# CLKB_power_regulators.net
KiCad netlist of a schematic drawn in Altium Designer
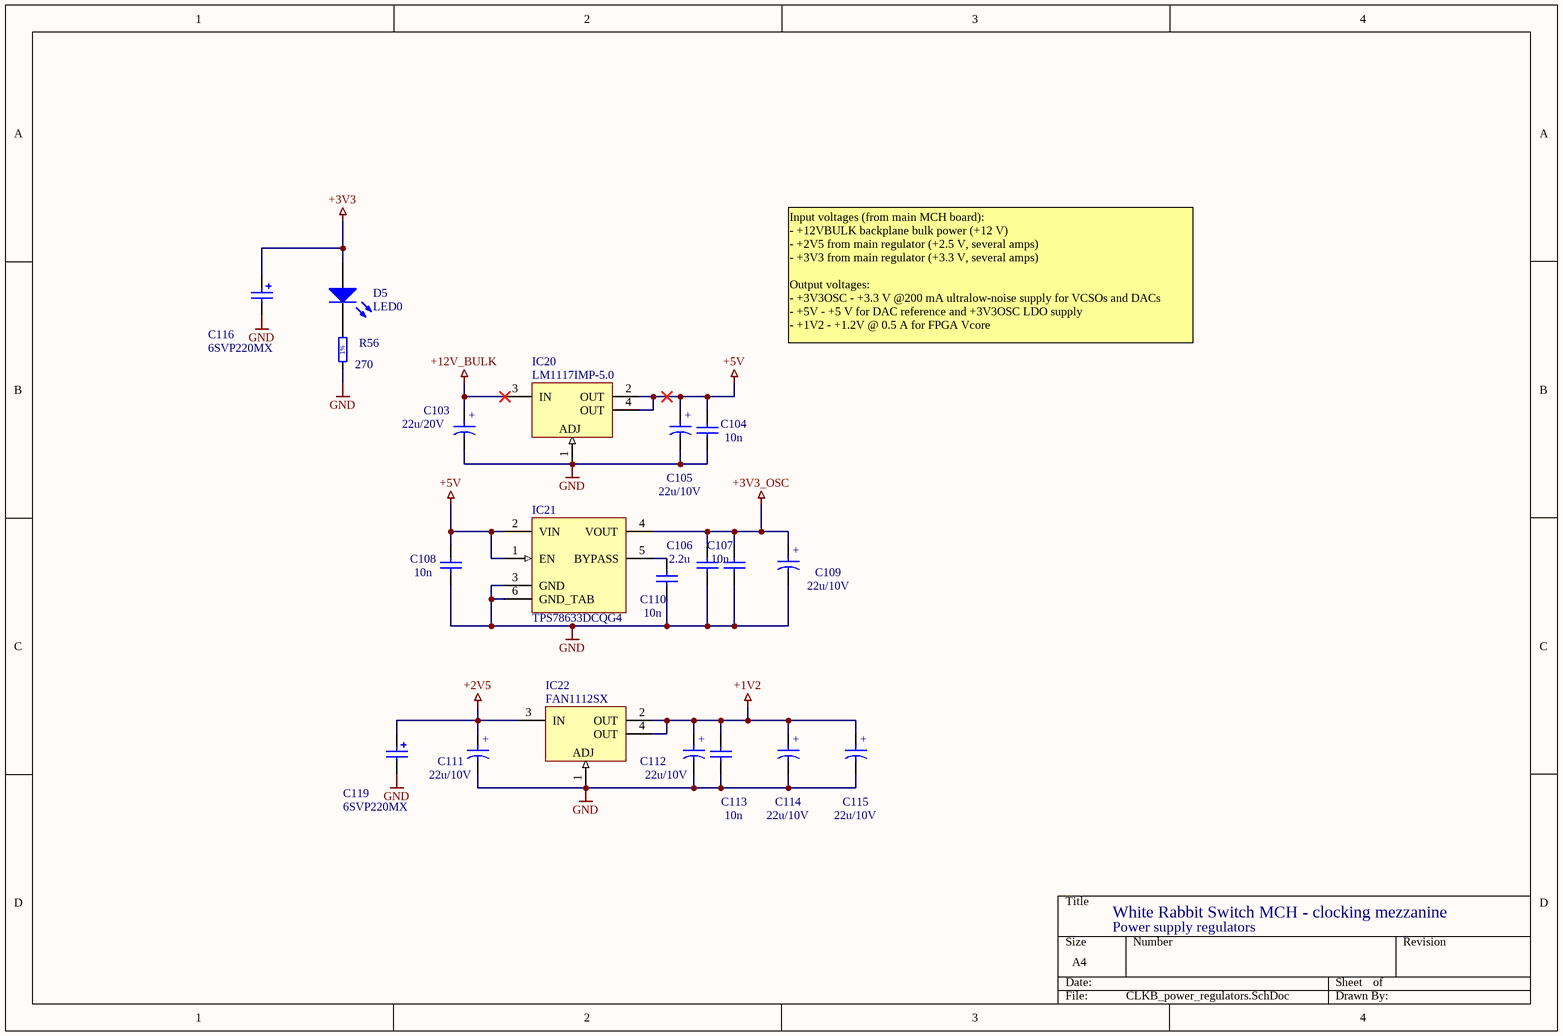
[diagram p0: CLKB_power_regulators.SchDoc]

(export (version "E")
  (design (tool "Eeschema 10.0.6"))
  (components
    (comp (ref "C103")
      (value "22u/20V")
      (footprint "CAPMP3528X210N")
      (description "Polarised capacitor")
      (fields
        (field (name "PART NUMBER") "CTE3528-21_22UF_20V_10%")
        (field (name "VOLTAGE") "20V")
        (field (name "AUTHOR") "CERN DEM JLC")
      )
      (libsource (lib "Capacitors") (part "Capacitor - polarized"))
    )
    (comp (ref "C104")
      (value "22u/10V")
      (footprint "CAPMP3216X180N")
      (description "Polarised capacitor")
      (fields
        (field (name "PART NUMBER") "CTE3216-18_22UF_10V_10%")
        (field (name "VOLTAGE") "10V")
        (field (name "AUTHOR") "CERN DEM JLC")
      )
      (libsource (lib "Capacitors") (part "Capacitor - polarized"))
    )
    (comp (ref "C105")
      (value "10n")
      (footprint "CAPC1608X87N")
      (description "Non-polarised capacitor")
      (fields
        (field (name "PART NUMBER") "CC0603_10NF_50V_10%_X7R")
        (field (name "VOLTAGE") "50V")
        (field (name "AUTHOR") "CERN DEM JLC")
      )
      (libsource (lib "Capacitors") (part "Capacitor - non polarized"))
    )
    (comp (ref "C106")
      (value "2.2u")
      (footprint "CAPC2012X135N")
      (description "Non-polarised capacitor")
      (fields
        (field (name "PART NUMBER") "CC0805_2.2UF_16V_10%_X7R")
        (field (name "VOLTAGE") "16V")
        (field (name "AUTHOR") "CERN DEM JLC")
      )
      (libsource (lib "Capacitors") (part "Capacitor - non polarized"))
    )
    (comp (ref "C107")
      (value "10n")
      (footprint "CAPC1608X87N")
      (description "Non-polarised capacitor")
      (fields
        (field (name "PART NUMBER") "CC0603_10NF_50V_10%_X7R")
        (field (name "VOLTAGE") "50V")
        (field (name "AUTHOR") "CERN DEM JLC")
      )
      (libsource (lib "Capacitors") (part "Capacitor - non polarized"))
    )
    (comp (ref "C108")
      (value "10n")
      (footprint "CAPC1608X87N")
      (description "Non-polarised capacitor")
      (fields
        (field (name "PART NUMBER") "CC0603_10NF_50V_10%_X7R")
        (field (name "VOLTAGE") "50V")
        (field (name "AUTHOR") "CERN DEM JLC")
      )
      (libsource (lib "Capacitors") (part "Capacitor - non polarized"))
    )
    (comp (ref "C109")
      (value "22u/10V")
      (footprint "CAPMP3216X180N")
      (description "Polarised capacitor")
      (fields
        (field (name "PART NUMBER") "CTE3216-18_22UF_10V_10%")
        (field (name "VOLTAGE") "10V")
        (field (name "AUTHOR") "CERN DEM JLC")
      )
      (libsource (lib "Capacitors") (part "Capacitor - polarized"))
    )
    (comp (ref "C110")
      (value "10n")
      (footprint "CAPC1608X87N")
      (description "Non-polarised capacitor")
      (fields
        (field (name "PART NUMBER") "CC0603_10NF_50V_10%_X7R")
        (field (name "VOLTAGE") "50V")
        (field (name "AUTHOR") "CERN DEM JLC")
      )
      (libsource (lib "Capacitors") (part "Capacitor - non polarized"))
    )
    (comp (ref "C111")
      (value "22u/10V")
      (footprint "CAPMP3216X180N")
      (description "Polarised capacitor")
      (fields
        (field (name "PART NUMBER") "CTE3216-18_22UF_10V_10%")
        (field (name "VOLTAGE") "10V")
        (field (name "AUTHOR") "CERN DEM JLC")
      )
      (libsource (lib "Capacitors") (part "Capacitor - polarized"))
    )
    (comp (ref "C112")
      (value "10n")
      (footprint "CAPC1608X87N")
      (description "Non-polarised capacitor")
      (fields
        (field (name "PART NUMBER") "CC0603_10NF_50V_10%_X7R")
        (field (name "VOLTAGE") "50V")
        (field (name "AUTHOR") "CERN DEM JLC")
      )
      (libsource (lib "Capacitors") (part "Capacitor - non polarized"))
    )
    (comp (ref "C113")
      (value "22u/10V")
      (footprint "CAPMP3216X180N")
      (description "Polarised capacitor")
      (fields
        (field (name "PART NUMBER") "CTE3216-18_22UF_10V_10%")
        (field (name "VOLTAGE") "10V")
        (field (name "AUTHOR") "CERN DEM JLC")
      )
      (libsource (lib "Capacitors") (part "Capacitor - polarized"))
    )
    (comp (ref "C114")
      (value "22u/10V")
      (footprint "CAPMP3216X180N")
      (description "Polarised capacitor")
      (fields
        (field (name "PART NUMBER") "CTE3216-18_22UF_10V_10%")
        (field (name "VOLTAGE") "10V")
        (field (name "AUTHOR") "CERN DEM JLC")
      )
      (libsource (lib "Capacitors") (part "Capacitor - polarized"))
    )
    (comp (ref "C115")
      (value "22u/10V")
      (footprint "CAPMP3216X180N")
      (description "Polarised capacitor")
      (fields
        (field (name "PART NUMBER") "CTE3216-18_22UF_10V_10%")
        (field (name "VOLTAGE") "10V")
        (field (name "AUTHOR") "CERN DEM JLC")
      )
      (libsource (lib "Capacitors") (part "Capacitor - polarized"))
    )
    (comp (ref "C116")
      (value "6SVP220MX")
      (footprint "OSCON_E7")
      (description "Polarized Capacitor (Radial)")
      (fields (field (name "Comment") "Cap Pol1") (field (name "PUBLISHER") "Altium Limited"))
      (libsource (lib "wr_switch") (part "Cap Pol1"))
    )
    (comp (ref "C119")
      (value "6SVP220MX")
      (footprint "OSCON_E7")
      (description "Polarized Capacitor (Radial)")
      (fields (field (name "Comment") "Cap Pol1") (field (name "PUBLISHER") "Altium Limited"))
      (libsource (lib "wr_switch") (part "Cap Pol1"))
    )
    (comp (ref "D5")
      (value "LED0")
      (footprint "CD1608-0603")
      (description "Red chip LED")
      (fields (field (name "PUBLISHER") "Altium Limited"))
      (libsource (lib "Miscellaneous Devices") (part "LED0"))
    )
    (comp (ref "IC20")
      (value "LM1117IMP-5.0")
      (footprint "SOT223-4L")
      (description "Three-Terminal Adjustable Output Positive Voltage Regulator")
      (fields (field (name "Comment") "LM1117") (field (name "PUBLISHER") "Altium Limited"))
      (libsource (lib "wr_switch") (part "1117"))
    )
    (comp (ref "IC21")
      (value "TPS78633DCQG4")
      (footprint "SOT223-6L")
      (description "TI low noise LDO, 1A load")
      (fields (field (name "Comment") "TPS786xx"))
      (libsource (lib "wr_switch") (part "TPS786xx"))
    )
    (comp (ref "IC22")
      (value "FAN1112SX")
      (footprint "SOT223-4L")
      (description "Three-Terminal Adjustable Output Positive Voltage Regulator")
      (fields (field (name "Comment") "LM1117") (field (name "PUBLISHER") "Altium Limited"))
      (libsource (lib "wr_switch") (part "1117"))
    )
    (comp (ref "R56")
      (value "270")
      (footprint "RESC1608X55N")
      (description "Resistor - 1%")
      (fields
        (field (name "PART NUMBER") "R0603_270R_1%_0.1W_100PPM")
        (field (name "POWER") "0.1W")
        (field (name "AUTHOR") "CERN DEM JLC")
      )
      (libsource (lib "Resistors") (part "Resistor - 1%"))
    )
  )
  (nets
    (net (code "1") (name "+1V2") (class "Default")
      (node (ref "C112") (pin "2") (pinfunction "2_2") (pintype "passive"))
      (node (ref "C113") (pin "1") (pinfunction "1_1") (pintype "passive"))
      (node (ref "C114") (pin "1") (pinfunction "1_1") (pintype "passive"))
      (node (ref "C115") (pin "1") (pinfunction "1_1") (pintype "passive"))
      (node (ref "IC22") (pin "2") (pinfunction "OUT_2") (pintype "power_in"))
      (node (ref "IC22") (pin "4") (pinfunction "OUT_4") (pintype "power_in"))
    )
    (net (code "2") (name "+2V5") (class "Default")
      (node (ref "C111") (pin "1") (pinfunction "1_1") (pintype "passive"))
      (node (ref "C119") (pin "1") (pinfunction "1_1") (pintype "passive"))
      (node (ref "IC22") (pin "3") (pinfunction "IN_3") (pintype "power_in"))
    )
    (net (code "3") (name "+3V3") (class "Default")
      (node (ref "C116") (pin "1") (pinfunction "1_1") (pintype "passive"))
      (node (ref "D5") (pin "1") (pinfunction "A_1") (pintype "passive"))
    )
    (net (code "4") (name "+3V3_OSC") (class "Default")
      (node (ref "C106") (pin "2") (pinfunction "2_2") (pintype "passive"))
      (node (ref "C107") (pin "2") (pinfunction "2_2") (pintype "passive"))
      (node (ref "C109") (pin "1") (pinfunction "1_1") (pintype "passive"))
      (node (ref "IC21") (pin "4") (pinfunction "VOUT_4") (pintype "power_in"))
    )
    (net (code "5") (name "+5V") (class "Default")
      (node (ref "C104") (pin "1") (pinfunction "1_1") (pintype "passive"))
      (node (ref "C105") (pin "2") (pinfunction "2_2") (pintype "passive"))
      (node (ref "C108") (pin "2") (pinfunction "2_2") (pintype "passive"))
      (node (ref "IC20") (pin "2") (pinfunction "OUT_2") (pintype "power_in"))
      (node (ref "IC20") (pin "4") (pinfunction "OUT_4") (pintype "power_in"))
      (node (ref "IC21") (pin "1") (pinfunction "EN_1") (pintype "input"))
      (node (ref "IC21") (pin "2") (pinfunction "VIN_2") (pintype "open_emitter"))
    )
    (net (code "6") (name "+12V_BULK") (class "Default")
      (node (ref "C103") (pin "1") (pinfunction "1_1") (pintype "passive"))
      (node (ref "IC20") (pin "3") (pinfunction "IN_3") (pintype "power_in"))
    )
    (net (code "7") (name "GND") (class "Default")
      (node (ref "C103") (pin "2") (pinfunction "2_2") (pintype "passive"))
      (node (ref "C104") (pin "2") (pinfunction "2_2") (pintype "passive"))
      (node (ref "C105") (pin "1") (pinfunction "1_1") (pintype "passive"))
      (node (ref "C106") (pin "1") (pinfunction "1_1") (pintype "passive"))
      (node (ref "C107") (pin "1") (pinfunction "1_1") (pintype "passive"))
      (node (ref "C108") (pin "1") (pinfunction "1_1") (pintype "passive"))
      (node (ref "C109") (pin "2") (pinfunction "2_2") (pintype "passive"))
      (node (ref "C110") (pin "1") (pinfunction "1_1") (pintype "passive"))
      (node (ref "C111") (pin "2") (pinfunction "2_2") (pintype "passive"))
      (node (ref "C112") (pin "1") (pinfunction "1_1") (pintype "passive"))
      (node (ref "C113") (pin "2") (pinfunction "2_2") (pintype "passive"))
      (node (ref "C114") (pin "2") (pinfunction "2_2") (pintype "passive"))
      (node (ref "C115") (pin "2") (pinfunction "2_2") (pintype "passive"))
      (node (ref "C116") (pin "2") (pinfunction "2_2") (pintype "passive"))
      (node (ref "C119") (pin "2") (pinfunction "2_2") (pintype "passive"))
      (node (ref "IC20") (pin "1") (pinfunction "ADJ_1") (pintype "input"))
      (node (ref "IC21") (pin "3") (pinfunction "GND_3") (pintype "passive"))
      (node (ref "IC21") (pin "6") (pinfunction "GND_TAB_6") (pintype "passive"))
      (node (ref "IC22") (pin "1") (pinfunction "ADJ_1") (pintype "input"))
      (node (ref "R56") (pin "1") (pinfunction "1_1") (pintype "passive"))
    )
    (net (code "8") (name "Net-(D5-K)") (class "Default")
      (node (ref "D5") (pin "2") (pinfunction "K_2") (pintype "passive"))
      (node (ref "R56") (pin "2") (pinfunction "2_2") (pintype "passive"))
    )
    (net (code "9") (name "Net-(IC21-BYPASS)") (class "Default")
      (node (ref "C110") (pin "2") (pinfunction "2_2") (pintype "passive"))
      (node (ref "IC21") (pin "5") (pinfunction "BYPASS_5") (pintype "passive"))
    )
  )
)
